# CAN.net
KiCad netlist of a schematic drawn in Altium Designer
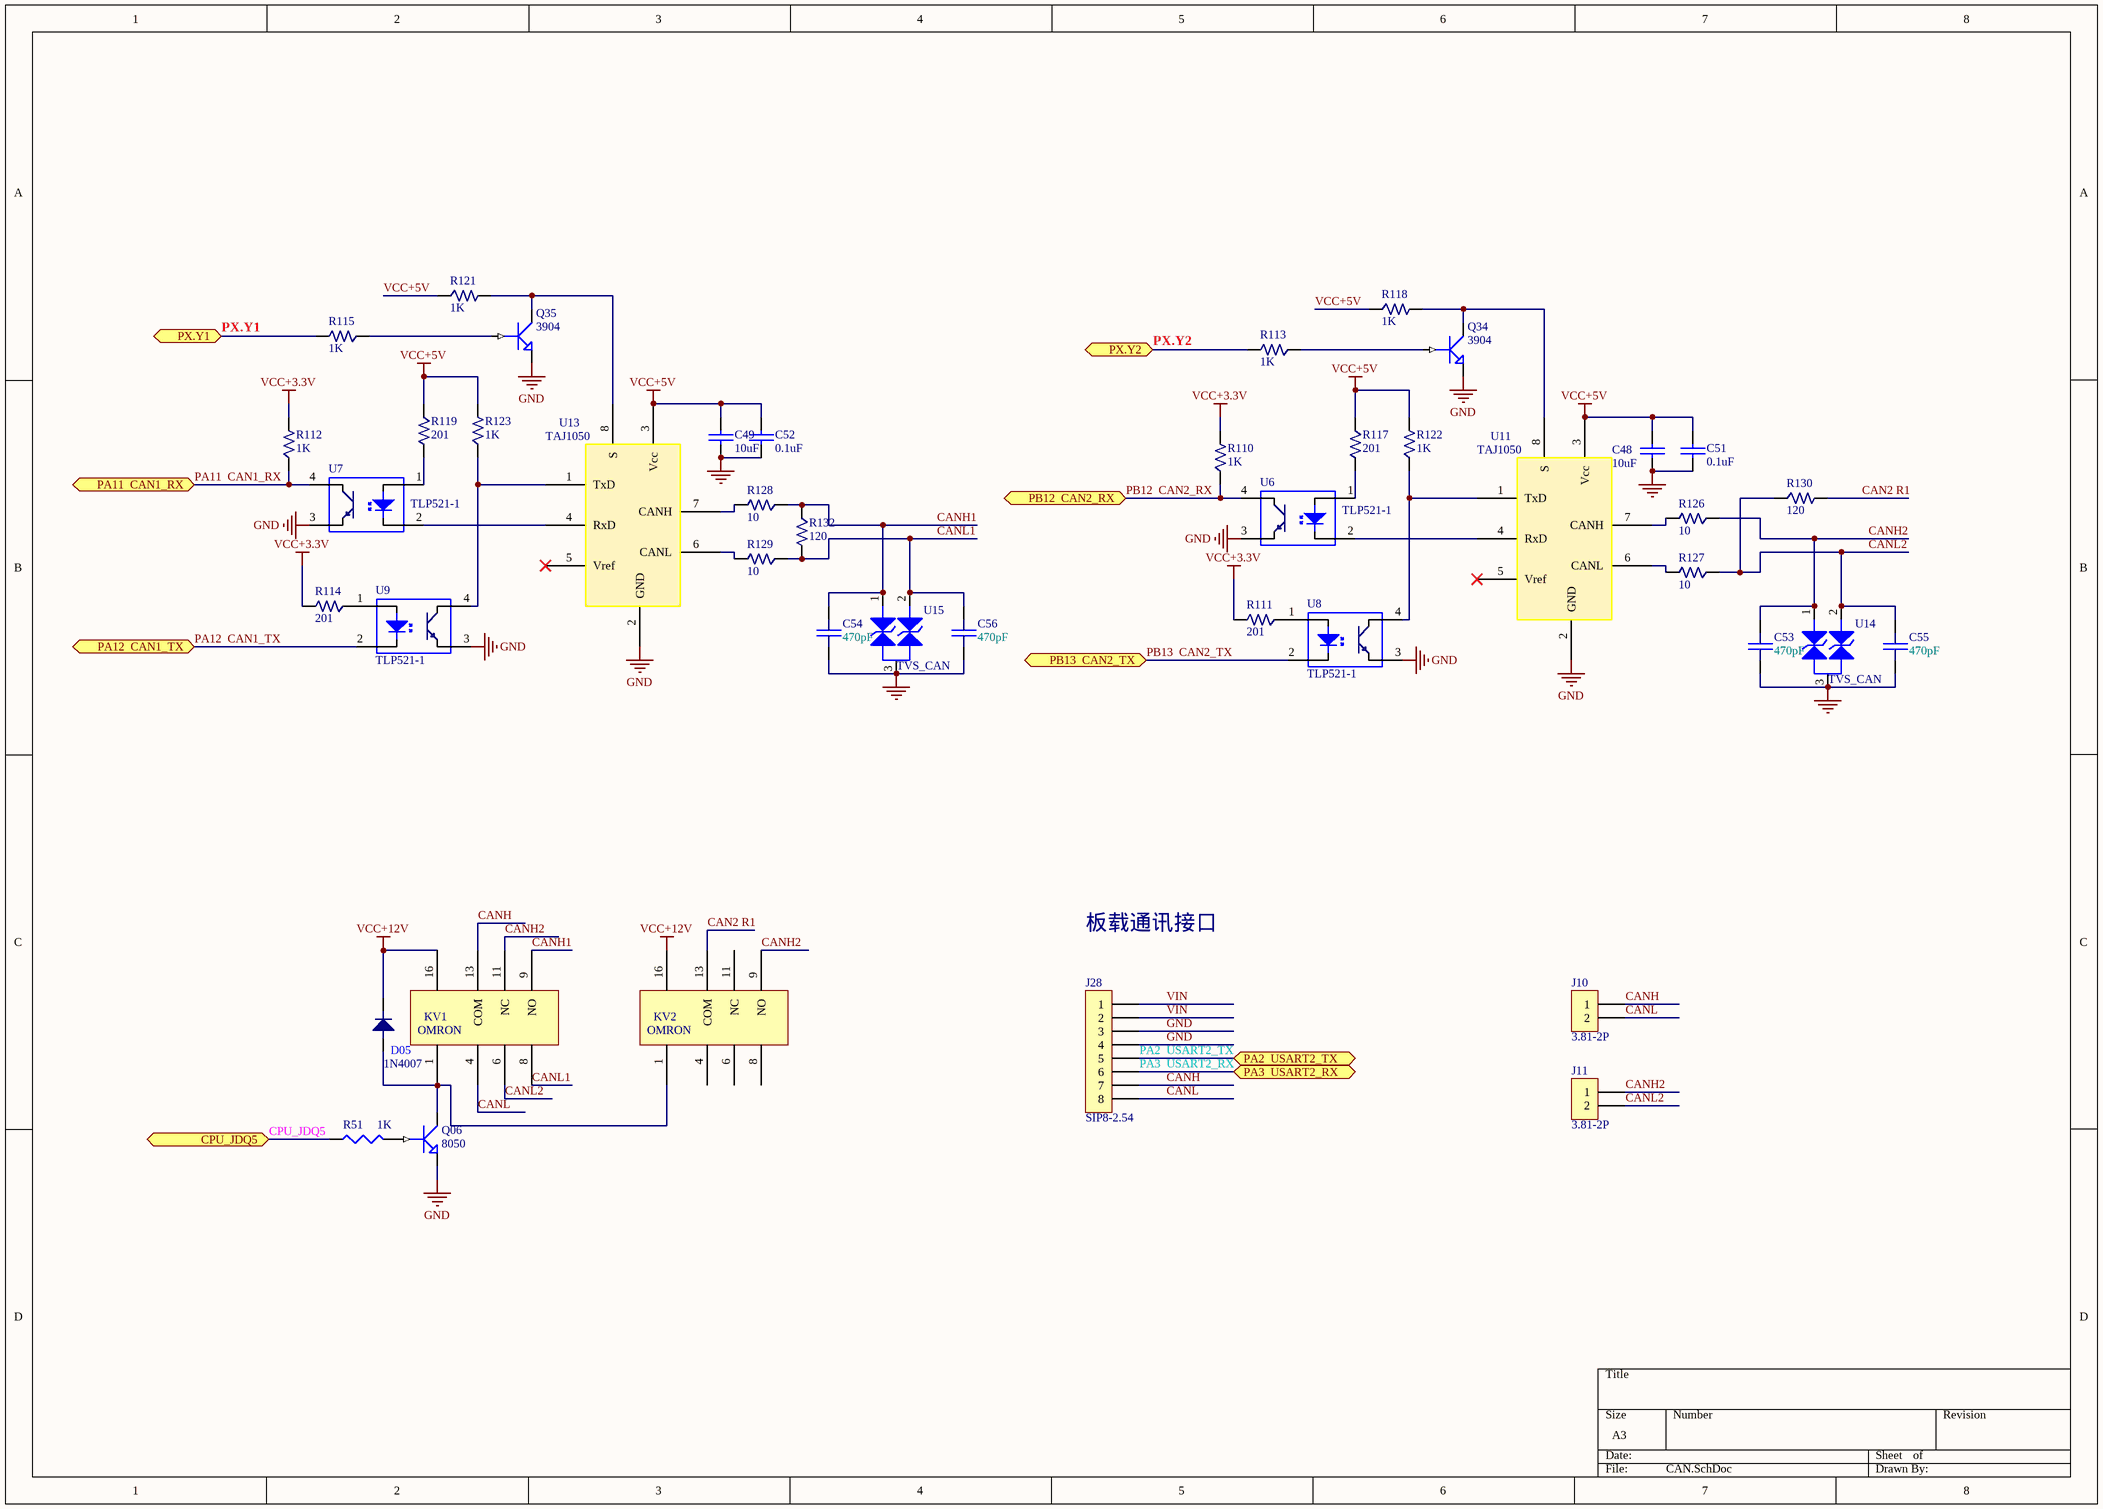
[diagram p0: CAN.SchDoc]

(export (version "E")
  (design (tool "Eeschema 10.0.6"))
  (components
    (comp (ref "C48") (value "10uF") (footprint "0805") (libsource (lib "INSPUR_SCH") (part "CAP")))
    (comp (ref "C49") (value "10uF") (footprint "0805") (libsource (lib "INSPUR_SCH") (part "CAP")))
    (comp (ref "C51") (value "0.1uF") (footprint "0603") (libsource (lib "INSPUR_SCH") (part "CAP")))
    (comp (ref "C52") (value "0.1uF") (footprint "0603") (libsource (lib "INSPUR_SCH") (part "CAP")))
    (comp (ref "C53")
      (value "470pF")
      (footprint "0603")
      (description "陶瓷电容")
      (libsource (lib "8CF_V6") (part "CAP"))
    )
    (comp (ref "C54")
      (value "470pF")
      (footprint "0603")
      (description "陶瓷电容")
      (libsource (lib "8CF_V6") (part "CAP"))
    )
    (comp (ref "C55")
      (value "470pF")
      (footprint "0603")
      (description "陶瓷电容")
      (libsource (lib "8CF_V6") (part "CAP"))
    )
    (comp (ref "C56")
      (value "470pF")
      (footprint "0603")
      (description "陶瓷电容")
      (libsource (lib "8CF_V6") (part "CAP"))
    )
    (comp (ref "D05")
      (value "1N4007")
      (footprint "DO-214AC(SMA)")
      (description "1A整流二极管")
      (libsource (lib "mylib") (part "1N4007"))
    )
    (comp (ref "J10")
      (value "3.81-2P")
      (footprint "3.81-2P")
      (libsource (lib "INSPUR_SCH") (part "SIP2A-2.50（带槽）"))
    )
    (comp (ref "J11")
      (value "3.81-2P")
      (footprint "3.81-2P")
      (libsource (lib "INSPUR_SCH") (part "SIP2A-2.50（带槽）"))
    )
    (comp (ref "J28")
      (value "SIP8-2.54")
      (footprint "2.54-8")
      (libsource (lib "INSPUR_PCB") (part "SIP8-2.54"))
    )
    (comp (ref "KV1")
      (value "OMRON")
      (footprint "KV")
      (description "omron G5V-2 12VDC")
      (libsource (lib "INSPUR_SCH") (part "OMRON"))
    )
    (comp (ref "KV2")
      (value "OMRON")
      (footprint "KV")
      (description "omron G5V-2 12VDC")
      (libsource (lib "INSPUR_SCH") (part "OMRON"))
    )
    (comp (ref "Q06") (value "8050") (footprint "SOT-23") (libsource (lib "INSPUR_SCH") (part "NPN1")))
    (comp (ref "Q34") (value "3904") (footprint "SOT-23") (libsource (lib "INSPUR_SCH") (part "NPN1")))
    (comp (ref "Q35") (value "3904") (footprint "SOT-23") (libsource (lib "INSPUR_SCH") (part "NPN1")))
    (comp (ref "R51") (value "1K") (footprint "0603") (libsource (lib "INSPUR_SCH") (part "RES1")))
    (comp (ref "R110")
      (value "1K")
      (footprint "0603")
      (description "高精度电阻")
      (libsource (lib "8CF_V6") (part "RES-1%"))
    )
    (comp (ref "R111")
      (value "201")
      (footprint "0603")
      (description "高精度电阻")
      (libsource (lib "8CF_V6") (part "RES-1%"))
    )
    (comp (ref "R112")
      (value "1K")
      (footprint "0603")
      (description "高精度电阻")
      (libsource (lib "8CF_V6") (part "RES-1%"))
    )
    (comp (ref "R113")
      (value "1K")
      (footprint "0603")
      (description "高精度电阻")
      (libsource (lib "8CF_V6") (part "RES-1%"))
    )
    (comp (ref "R114")
      (value "201")
      (footprint "0603")
      (description "高精度电阻")
      (libsource (lib "8CF_V6") (part "RES-1%"))
    )
    (comp (ref "R115")
      (value "1K")
      (footprint "0603")
      (description "高精度电阻")
      (libsource (lib "8CF_V6") (part "RES-1%"))
    )
    (comp (ref "R117")
      (value "201")
      (footprint "0603")
      (description "高精度电阻")
      (libsource (lib "8CF_V6") (part "RES-1%"))
    )
    (comp (ref "R118")
      (value "1K")
      (footprint "0603")
      (description "高精度电阻")
      (libsource (lib "8CF_V6") (part "RES-1%"))
    )
    (comp (ref "R119")
      (value "201")
      (footprint "0603")
      (description "高精度电阻")
      (libsource (lib "8CF_V6") (part "RES-1%"))
    )
    (comp (ref "R121")
      (value "1K")
      (footprint "0603")
      (description "高精度电阻")
      (libsource (lib "8CF_V6") (part "RES-1%"))
    )
    (comp (ref "R122")
      (value "1K")
      (footprint "0603")
      (description "高精度电阻")
      (libsource (lib "8CF_V6") (part "RES-1%"))
    )
    (comp (ref "R123")
      (value "1K")
      (footprint "0603")
      (description "高精度电阻")
      (libsource (lib "8CF_V6") (part "RES-1%"))
    )
    (comp (ref "R126")
      (value "10")
      (footprint "0603")
      (description "高精度电阻")
      (libsource (lib "8CF_V6") (part "RES-1%"))
    )
    (comp (ref "R127")
      (value "10")
      (footprint "0603")
      (description "高精度电阻")
      (libsource (lib "8CF_V6") (part "RES-1%"))
    )
    (comp (ref "R128")
      (value "10")
      (footprint "0603")
      (description "高精度电阻")
      (libsource (lib "8CF_V6") (part "RES-1%"))
    )
    (comp (ref "R129")
      (value "10")
      (footprint "0603")
      (description "高精度电阻")
      (libsource (lib "8CF_V6") (part "RES-1%"))
    )
    (comp (ref "R130")
      (value "120")
      (footprint "0603")
      (description "高精度电阻")
      (libsource (lib "8CF_V6") (part "RES-1%"))
    )
    (comp (ref "R132")
      (value "120")
      (footprint "0603")
      (description "高精度电阻")
      (libsource (lib "8CF_V6") (part "RES-1%"))
    )
    (comp (ref "U6")
      (value "TLP521-1")
      (footprint "DIP4")
      (description "光耦")
      (libsource (lib "mylib") (part "TLP521"))
    )
    (comp (ref "U7")
      (value "TLP521-1")
      (footprint "DIP4")
      (description "光耦")
      (libsource (lib "mylib") (part "TLP521"))
    )
    (comp (ref "U8")
      (value "TLP521-1")
      (footprint "DIP4")
      (description "光耦")
      (libsource (lib "mylib") (part "TLP521"))
    )
    (comp (ref "U9")
      (value "TLP521-1")
      (footprint "DIP4")
      (description "光耦")
      (libsource (lib "mylib") (part "TLP521"))
    )
    (comp (ref "U11") (value "TAJ1050") (footprint "SO-8") (libsource (lib "INSPUR_SCH") (part "TAJ1050")))
    (comp (ref "U13") (value "TAJ1050") (footprint "SO-8") (libsource (lib "INSPUR_SCH") (part "TAJ1050")))
    (comp (ref "U14")
      (value "TVS_CAN")
      (footprint "SOT-23")
      (description "NUP2105L")
      (libsource (lib "INSPUR_SCH") (part "TVS_CAN"))
    )
    (comp (ref "U15")
      (value "TVS_CAN")
      (footprint "SOT-23")
      (description "NUP2105L")
      (libsource (lib "INSPUR_SCH") (part "TVS_CAN"))
    )
  )
  (nets
    (net (code "1") (name "/CAN2 R1") (class "Default")
      (node (ref "KV2") (pin "13") (pinfunction "COM_13") (pintype "passive"))
      (node (ref "R130") (pin "2") (pintype "passive"))
    )
    (net (code "2") (name "/CANH") (class "Default")
      (node (ref "J10") (pin "1") (pinfunction "1_1") (pintype "passive"))
      (node (ref "J28") (pin "7") (pinfunction "7_7") (pintype "passive"))
      (node (ref "KV1") (pin "13") (pinfunction "COM_13") (pintype "passive"))
    )
    (net (code "3") (name "/CANH1") (class "Default")
      (node (ref "C54") (pin "1") (pintype "passive"))
      (node (ref "KV1") (pin "9") (pinfunction "NO_9") (pintype "passive"))
      (node (ref "R128") (pin "1") (pintype "passive"))
      (node (ref "R132") (pin "1") (pintype "passive"))
      (node (ref "U15") (pin "1") (pintype "passive"))
    )
    (net (code "4") (name "/CANH2") (class "Default")
      (node (ref "C53") (pin "1") (pintype "passive"))
      (node (ref "J11") (pin "1") (pinfunction "1_1") (pintype "passive"))
      (node (ref "KV1") (pin "11") (pinfunction "NC_11") (pintype "passive"))
      (node (ref "KV2") (pin "9") (pinfunction "NO_9") (pintype "passive"))
      (node (ref "R126") (pin "1") (pintype "passive"))
      (node (ref "U14") (pin "1") (pintype "passive"))
    )
    (net (code "5") (name "/CANL") (class "Default")
      (node (ref "J10") (pin "2") (pinfunction "2_2") (pintype "passive"))
      (node (ref "J28") (pin "8") (pinfunction "8_8") (pintype "passive"))
      (node (ref "KV1") (pin "4") (pinfunction "1_4") (pintype "passive"))
    )
    (net (code "6") (name "/CANL1") (class "Default")
      (node (ref "C56") (pin "1") (pintype "passive"))
      (node (ref "KV1") (pin "8") (pinfunction "3_8") (pintype "passive"))
      (node (ref "R129") (pin "1") (pintype "passive"))
      (node (ref "R132") (pin "2") (pintype "passive"))
      (node (ref "U15") (pin "2") (pinfunction "K_2") (pintype "passive"))
    )
    (net (code "7") (name "/CANL2") (class "Default")
      (node (ref "C55") (pin "1") (pintype "passive"))
      (node (ref "J11") (pin "2") (pinfunction "2_2") (pintype "passive"))
      (node (ref "KV1") (pin "6") (pinfunction "2_6") (pintype "passive"))
      (node (ref "R127") (pin "1") (pintype "passive"))
      (node (ref "R130") (pin "1") (pintype "passive"))
      (node (ref "U14") (pin "2") (pinfunction "K_2") (pintype "passive"))
    )
    (net (code "8") (name "/CPU_JDQ5") (class "Default")
      (node (ref "R51") (pin "1") (pinfunction "1_1") (pintype "passive"))
    )
    (net (code "9") (name "/PA2  USART2_TX") (class "Default")
      (node (ref "J28") (pin "5") (pinfunction "5_5") (pintype "passive"))
    )
    (net (code "10") (name "/PA3  USART2_RX") (class "Default")
      (node (ref "J28") (pin "6") (pinfunction "6_6") (pintype "passive"))
    )
    (net (code "11") (name "/PA11  CAN1_RX") (class "Default")
      (node (ref "R112") (pin "1") (pintype "passive"))
      (node (ref "U7") (pin "4") (pinfunction "4_4") (pintype "passive"))
    )
    (net (code "12") (name "/PA12  CAN1_TX") (class "Default")
      (node (ref "U9") (pin "2") (pinfunction "2_2") (pintype "passive"))
    )
    (net (code "13") (name "/PB12  CAN2_RX") (class "Default")
      (node (ref "R110") (pin "1") (pintype "passive"))
      (node (ref "U6") (pin "4") (pinfunction "4_4") (pintype "passive"))
    )
    (net (code "14") (name "/PB13  CAN2_TX") (class "Default")
      (node (ref "U8") (pin "2") (pinfunction "2_2") (pintype "passive"))
    )
    (net (code "15") (name "/PX.Y1") (class "Default") (node (ref "R115") (pin "2") (pintype "passive")))
    (net (code "16") (name "/PX.Y2") (class "Default") (node (ref "R113") (pin "2") (pintype "passive")))
    (net (code "17") (name "/VIN") (class "Default")
      (node (ref "J28") (pin "1") (pinfunction "1_1") (pintype "passive"))
      (node (ref "J28") (pin "2") (pinfunction "2_2") (pintype "passive"))
    )
    (net (code "18") (name "GND") (class "Default")
      (node (ref "C48") (pin "1") (pinfunction "1_1") (pintype "passive"))
      (node (ref "C49") (pin "1") (pinfunction "1_1") (pintype "passive"))
      (node (ref "C51") (pin "1") (pinfunction "1_1") (pintype "passive"))
      (node (ref "C52") (pin "1") (pinfunction "1_1") (pintype "passive"))
      (node (ref "C53") (pin "2") (pintype "passive"))
      (node (ref "C54") (pin "2") (pintype "passive"))
      (node (ref "C55") (pin "2") (pintype "passive"))
      (node (ref "C56") (pin "2") (pintype "passive"))
      (node (ref "J28") (pin "3") (pinfunction "3_3") (pintype "passive"))
      (node (ref "J28") (pin "4") (pinfunction "4_4") (pintype "passive"))
      (node (ref "Q06") (pin "2") (pinfunction "E_2") (pintype "passive"))
      (node (ref "Q34") (pin "2") (pinfunction "E_2") (pintype "passive"))
      (node (ref "Q35") (pin "2") (pinfunction "E_2") (pintype "passive"))
      (node (ref "U11") (pin "2") (pinfunction "GND_2") (pintype "passive"))
      (node (ref "U13") (pin "2") (pinfunction "GND_2") (pintype "passive"))
      (node (ref "U14") (pin "3") (pintype "passive"))
      (node (ref "U15") (pin "3") (pintype "passive"))
      (node (ref "U6") (pin "3") (pinfunction "3_3") (pintype "passive"))
      (node (ref "U7") (pin "3") (pinfunction "3_3") (pintype "passive"))
      (node (ref "U8") (pin "3") (pinfunction "3_3") (pintype "passive"))
      (node (ref "U9") (pin "3") (pinfunction "3_3") (pintype "passive"))
    )
    (net (code "19") (name "Net-(Q06-B)") (class "Default")
      (node (ref "Q06") (pin "1") (pinfunction "B_1") (pintype "input"))
      (node (ref "R51") (pin "2") (pinfunction "2_2") (pintype "passive"))
    )
    (net (code "20") (name "Net-(Q06-C)") (class "Default")
      (node (ref "D05") (pin "1") (pintype "passive"))
      (node (ref "KV1") (pin "1") (pintype "passive"))
      (node (ref "KV2") (pin "1") (pintype "passive"))
      (node (ref "Q06") (pin "3") (pinfunction "C_3") (pintype "passive"))
    )
    (net (code "21") (name "Net-(Q34-B)") (class "Default")
      (node (ref "Q34") (pin "1") (pinfunction "B_1") (pintype "input"))
      (node (ref "R113") (pin "1") (pintype "passive"))
    )
    (net (code "22") (name "Net-(Q34-C)") (class "Default")
      (node (ref "Q34") (pin "3") (pinfunction "C_3") (pintype "passive"))
      (node (ref "R118") (pin "2") (pintype "passive"))
      (node (ref "U11") (pin "8") (pinfunction "S_8") (pintype "passive"))
    )
    (net (code "23") (name "Net-(Q35-B)") (class "Default")
      (node (ref "Q35") (pin "1") (pinfunction "B_1") (pintype "input"))
      (node (ref "R115") (pin "1") (pintype "passive"))
    )
    (net (code "24") (name "Net-(Q35-C)") (class "Default")
      (node (ref "Q35") (pin "3") (pinfunction "C_3") (pintype "passive"))
      (node (ref "R121") (pin "2") (pintype "passive"))
      (node (ref "U13") (pin "8") (pinfunction "S_8") (pintype "passive"))
    )
    (net (code "25") (name "Net-(R111-Pad1)") (class "Default")
      (node (ref "R111") (pin "1") (pintype "passive"))
      (node (ref "U8") (pin "1") (pinfunction "1_1") (pintype "passive"))
    )
    (net (code "26") (name "Net-(R114-Pad1)") (class "Default")
      (node (ref "R114") (pin "1") (pintype "passive"))
      (node (ref "U9") (pin "1") (pinfunction "1_1") (pintype "passive"))
    )
    (net (code "27") (name "Net-(R117-Pad2)") (class "Default")
      (node (ref "R117") (pin "2") (pintype "passive"))
      (node (ref "U6") (pin "1") (pinfunction "1_1") (pintype "passive"))
    )
    (net (code "28") (name "Net-(R119-Pad2)") (class "Default")
      (node (ref "R119") (pin "2") (pintype "passive"))
      (node (ref "U7") (pin "1") (pinfunction "1_1") (pintype "passive"))
    )
    (net (code "29") (name "Net-(U11-CANH)") (class "Default")
      (node (ref "R126") (pin "2") (pintype "passive"))
      (node (ref "U11") (pin "7") (pinfunction "CANH_7") (pintype "passive"))
    )
    (net (code "30") (name "Net-(U11-CANL)") (class "Default")
      (node (ref "R127") (pin "2") (pintype "passive"))
      (node (ref "U11") (pin "6") (pinfunction "CANL_6") (pintype "passive"))
    )
    (net (code "31") (name "Net-(U11-RxD)") (class "Default")
      (node (ref "U11") (pin "4") (pinfunction "RxD_4") (pintype "passive"))
      (node (ref "U6") (pin "2") (pinfunction "2_2") (pintype "passive"))
    )
    (net (code "32") (name "Net-(U11-TxD)") (class "Default")
      (node (ref "R122") (pin "1") (pintype "passive"))
      (node (ref "U11") (pin "1") (pinfunction "TxD_1") (pintype "passive"))
      (node (ref "U8") (pin "4") (pinfunction "4_4") (pintype "passive"))
    )
    (net (code "33") (name "Net-(U13-CANH)") (class "Default")
      (node (ref "R128") (pin "2") (pintype "passive"))
      (node (ref "U13") (pin "7") (pinfunction "CANH_7") (pintype "passive"))
    )
    (net (code "34") (name "Net-(U13-CANL)") (class "Default")
      (node (ref "R129") (pin "2") (pintype "passive"))
      (node (ref "U13") (pin "6") (pinfunction "CANL_6") (pintype "passive"))
    )
    (net (code "35") (name "Net-(U13-RxD)") (class "Default")
      (node (ref "U13") (pin "4") (pinfunction "RxD_4") (pintype "passive"))
      (node (ref "U7") (pin "2") (pinfunction "2_2") (pintype "passive"))
    )
    (net (code "36") (name "Net-(U13-TxD)") (class "Default")
      (node (ref "R123") (pin "1") (pintype "passive"))
      (node (ref "U13") (pin "1") (pinfunction "TxD_1") (pintype "passive"))
      (node (ref "U9") (pin "4") (pinfunction "4_4") (pintype "passive"))
    )
    (net (code "37") (name "VCC+3.3V") (class "Default")
      (node (ref "R110") (pin "2") (pintype "passive"))
      (node (ref "R111") (pin "2") (pintype "passive"))
      (node (ref "R112") (pin "2") (pintype "passive"))
      (node (ref "R114") (pin "2") (pintype "passive"))
    )
    (net (code "38") (name "VCC+5V") (class "Default")
      (node (ref "C48") (pin "2") (pinfunction "2_2") (pintype "passive"))
      (node (ref "C49") (pin "2") (pinfunction "2_2") (pintype "passive"))
      (node (ref "C51") (pin "2") (pinfunction "2_2") (pintype "passive"))
      (node (ref "C52") (pin "2") (pinfunction "2_2") (pintype "passive"))
      (node (ref "R117") (pin "1") (pintype "passive"))
      (node (ref "R118") (pin "1") (pintype "passive"))
      (node (ref "R119") (pin "1") (pintype "passive"))
      (node (ref "R121") (pin "1") (pintype "passive"))
      (node (ref "R122") (pin "2") (pintype "passive"))
      (node (ref "R123") (pin "2") (pintype "passive"))
      (node (ref "U11") (pin "3") (pinfunction "Vcc_3") (pintype "passive"))
      (node (ref "U13") (pin "3") (pinfunction "Vcc_3") (pintype "passive"))
    )
    (net (code "39") (name "VCC+12V") (class "Default")
      (node (ref "D05") (pin "2") (pintype "passive"))
      (node (ref "KV1") (pin "16") (pintype "passive"))
      (node (ref "KV2") (pin "16") (pintype "passive"))
    )
    (net (code "40") (name "unconnected-(KV2-1-Pad4)") (class "Default")
      (node (ref "KV2") (pin "4") (pinfunction "1_4") (pintype "passive"))
    )
    (net (code "41") (name "unconnected-(KV2-2-Pad6)") (class "Default")
      (node (ref "KV2") (pin "6") (pinfunction "2_6") (pintype "passive"))
    )
    (net (code "42") (name "unconnected-(KV2-3-Pad8)") (class "Default")
      (node (ref "KV2") (pin "8") (pinfunction "3_8") (pintype "passive"))
    )
    (net (code "43") (name "unconnected-(KV2-NC-Pad11)") (class "Default")
      (node (ref "KV2") (pin "11") (pinfunction "NC_11") (pintype "passive"))
    )
    (net (code "44") (name "unconnected-(U11-Vref-Pad5)") (class "Default")
      (node (ref "U11") (pin "5") (pinfunction "Vref_5") (pintype "passive+no_connect"))
    )
    (net (code "45") (name "unconnected-(U13-Vref-Pad5)") (class "Default")
      (node (ref "U13") (pin "5") (pinfunction "Vref_5") (pintype "passive+no_connect"))
    )
  )
)
